# wootch_v_0_0.net
KiCad netlist of a schematic drawn in Altium Designer
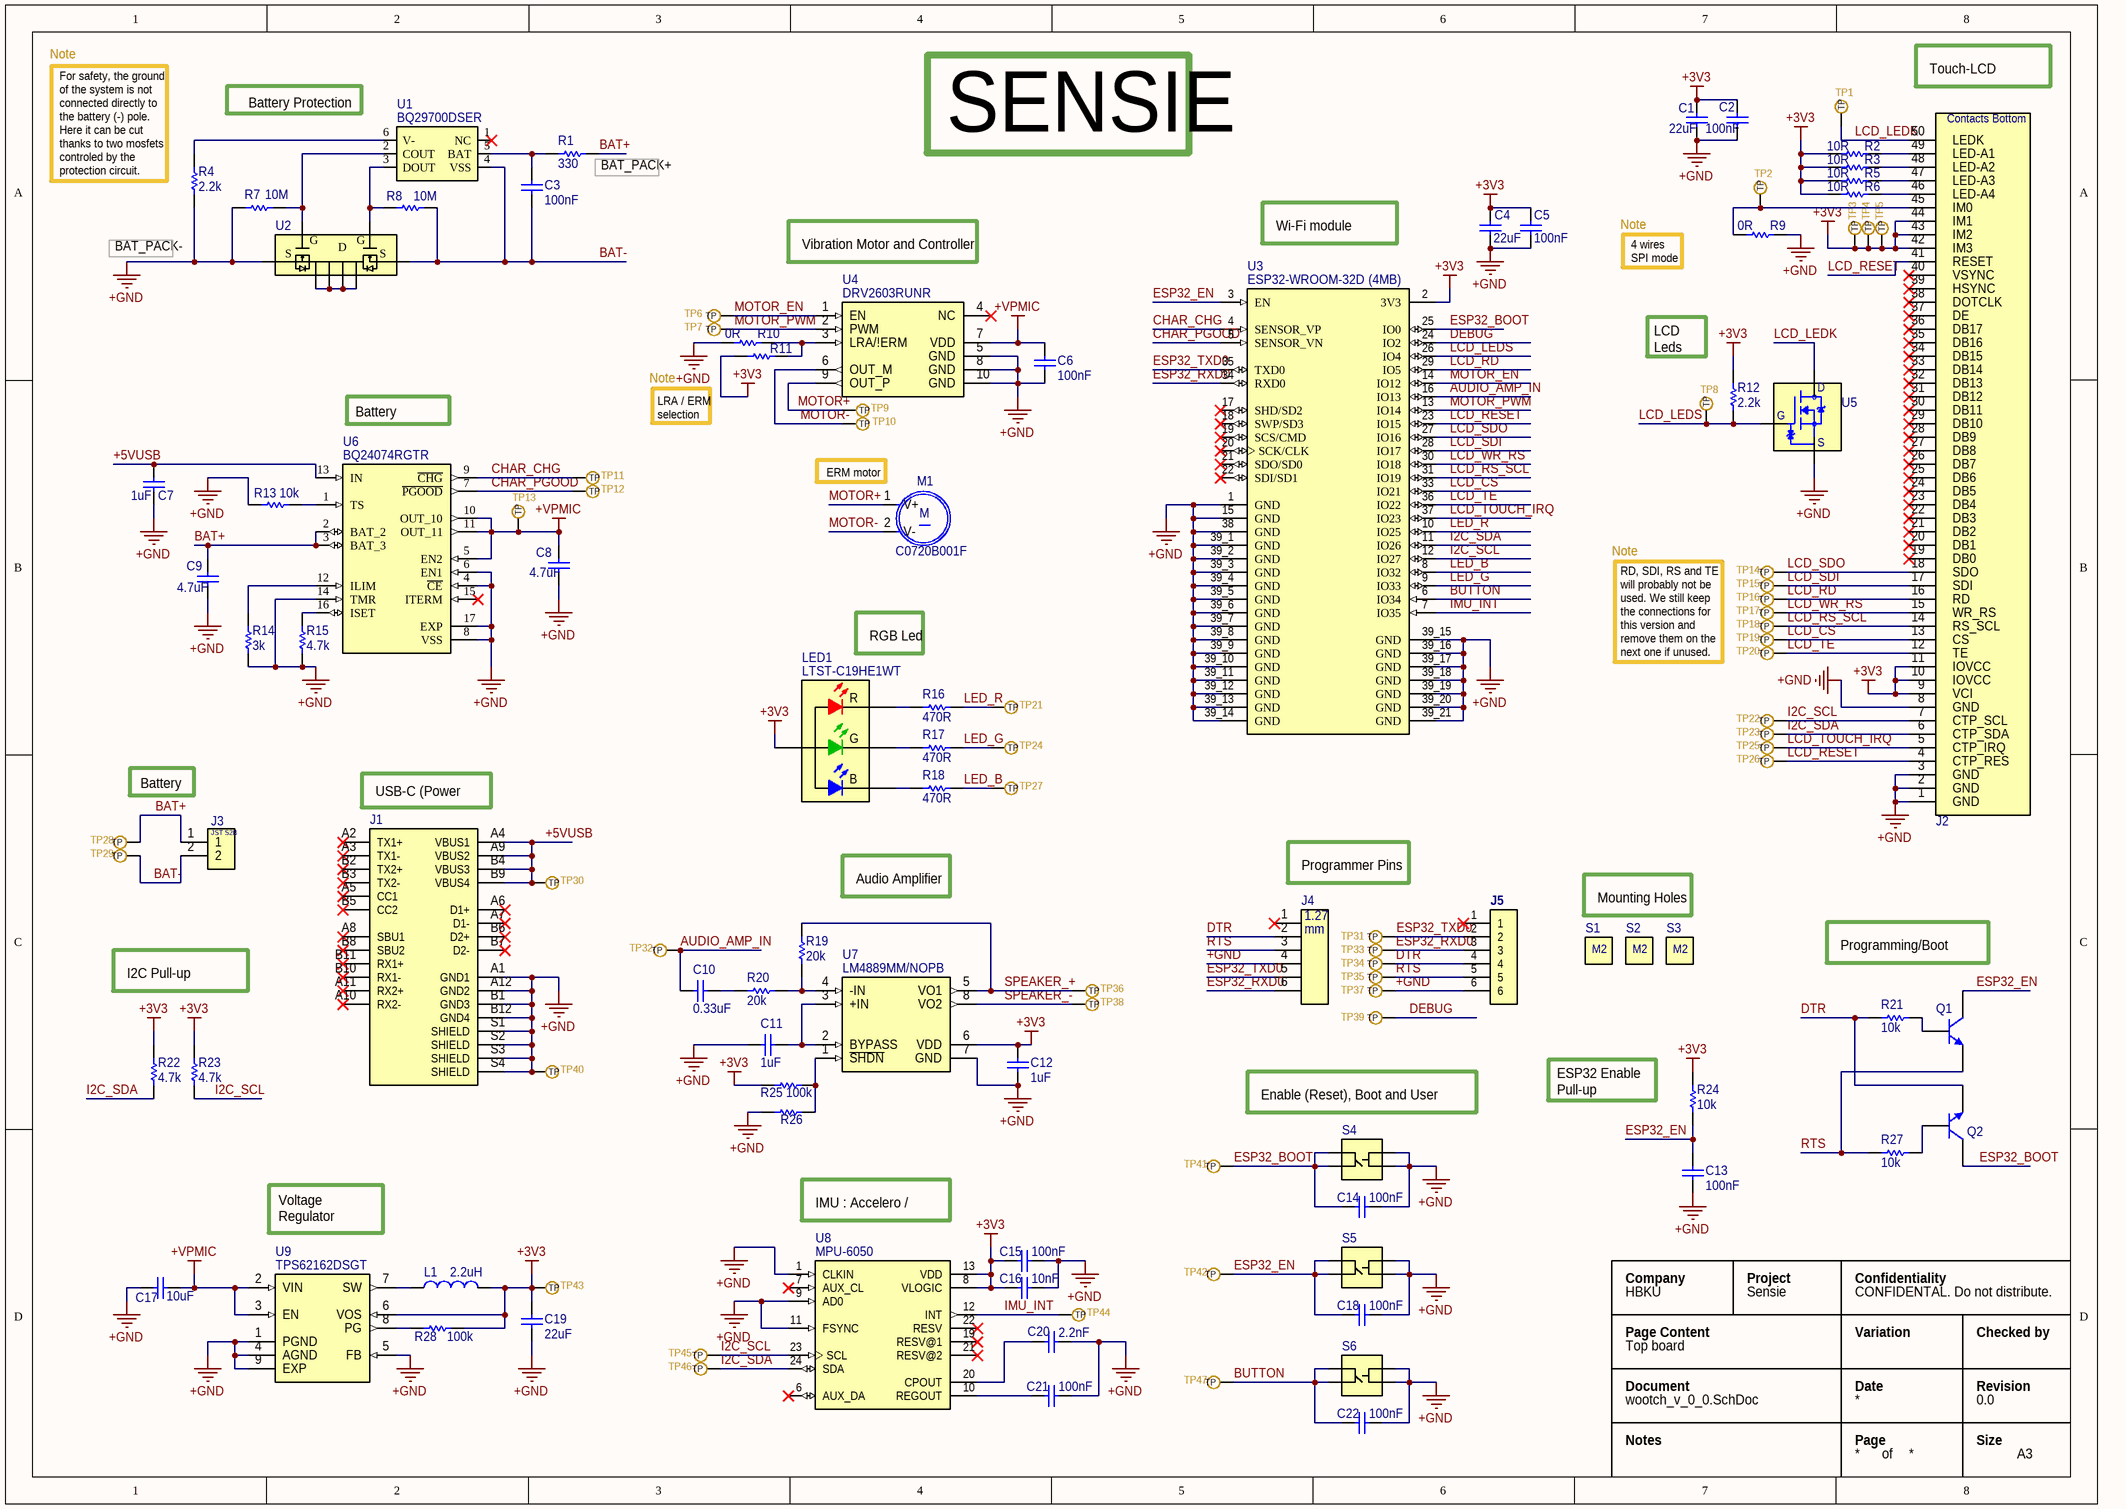
[diagram p0: wootch_v_0_0.SchDoc]

(export (version "E")
  (design (tool "Eeschema 10.0.6"))
  (components
    (comp (ref "C1")
      (value "22uF")
      (footprint "C0603")
      (description "CAP CER 22UF 6.3V X5R 0603")
      (fields
        (field (name "MANUFACTURER PART NUMBER") "GRM188R60J226MEA0D")
        (field (name "MANUFACTURER") "Murata Electronics")
      )
      (libsource (lib "rcl") (part "CAP 22uF 0603"))
    )
    (comp (ref "C2")
      (value "100nF")
      (footprint "C0402")
      (description "CAP CER 0.1UF 16V X7R 0402")
      (fields
        (field (name "MANUFACTURER PART NUMBER") "GRM155R71C104KA88J")
        (field (name "MANUFACTURER") "Murata Electronics")
      )
      (libsource (lib "rcl") (part "CAP 100nF 0402"))
    )
    (comp (ref "C3")
      (value "100nF")
      (footprint "C0402")
      (description "CAP CER 0.1UF 16V X7R 0402")
      (fields
        (field (name "MANUFACTURER PART NUMBER") "GRM155R71C104KA88J")
        (field (name "MANUFACTURER") "Murata Electronics")
      )
      (libsource (lib "rcl") (part "CAP 100nF 0402"))
    )
    (comp (ref "C4")
      (value "22uF")
      (footprint "C0603")
      (description "CAP CER 22UF 6.3V X5R 0603")
      (fields
        (field (name "MANUFACTURER PART NUMBER") "GRM188R60J226MEA0D")
        (field (name "MANUFACTURER") "Murata Electronics")
      )
      (libsource (lib "rcl") (part "CAP 22uF 0603"))
    )
    (comp (ref "C5")
      (value "100nF")
      (footprint "C0402")
      (description "CAP CER 0.1UF 16V X7R 0402")
      (fields
        (field (name "MANUFACTURER PART NUMBER") "GRM155R71C104KA88J")
        (field (name "MANUFACTURER") "Murata Electronics")
      )
      (libsource (lib "rcl") (part "CAP 100nF 0402"))
    )
    (comp (ref "C6")
      (value "100nF")
      (footprint "C0402")
      (description "CAP CER 0.1UF 16V X7R 0402")
      (fields
        (field (name "MANUFACTURER PART NUMBER") "GRM155R71C104KA88J")
        (field (name "MANUFACTURER") "Murata Electronics")
      )
      (libsource (lib "rcl") (part "CAP 100nF 0402"))
    )
    (comp (ref "C7")
      (value "1uF")
      (footprint "C0402")
      (description "CAP CER 1UF 10V X6S 0402")
      (fields
        (field (name "MANUFACTURER PART NUMBER") "GRM155C81A105KA12D")
        (field (name "MANUFACTURER") "Murata Electronics")
      )
      (libsource (lib "rcl") (part "CAP 1uF 0402"))
    )
    (comp (ref "C8")
      (value "4.7uF")
      (footprint "C0402")
      (description "CAP CER 4.7UF 6.3V X5R 0402")
      (fields
        (field (name "MANUFACTURER PART NUMBER") "GRM155R60J475ME47D")
        (field (name "MANUFACTURER") "Murata Electronics")
      )
      (libsource (lib "rcl") (part "CAP 4.7uF 0402"))
    )
    (comp (ref "C9")
      (value "4.7uF")
      (footprint "C0402")
      (description "CAP CER 4.7UF 6.3V X5R 0402")
      (fields
        (field (name "MANUFACTURER PART NUMBER") "GRM155R60J475ME47D")
        (field (name "MANUFACTURER") "Murata Electronics")
      )
      (libsource (lib "rcl") (part "CAP 4.7uF 0402"))
    )
    (comp (ref "C10")
      (value "0.33uF")
      (footprint "C0402")
      (description "CAP CER 0.33UF 10V X6S 0402")
      (fields
        (field (name "MANUFACTURER PART NUMBER") "GRM155R61A334KE15D")
        (field (name "MANUFACTURER") "Murata Electronics")
      )
      (libsource (lib "rcl") (part "CAP 0.33uF 0402"))
    )
    (comp (ref "C11")
      (value "1uF")
      (footprint "C0402")
      (description "CAP CER 1UF 10V X6S 0402")
      (fields
        (field (name "MANUFACTURER PART NUMBER") "GRM155C81A105KA12D")
        (field (name "MANUFACTURER") "Murata Electronics")
      )
      (libsource (lib "rcl") (part "CAP 1uF 0402"))
    )
    (comp (ref "C12")
      (value "1uF")
      (footprint "C0402")
      (description "CAP CER 1UF 10V X6S 0402")
      (fields
        (field (name "MANUFACTURER PART NUMBER") "GRM155C81A105KA12D")
        (field (name "MANUFACTURER") "Murata Electronics")
      )
      (libsource (lib "rcl") (part "CAP 1uF 0402"))
    )
    (comp (ref "C13")
      (value "100nF")
      (footprint "C0402")
      (description "CAP CER 0.1UF 16V X7R 0402")
      (fields
        (field (name "MANUFACTURER PART NUMBER") "GRM155R71C104KA88J")
        (field (name "MANUFACTURER") "Murata Electronics")
      )
      (libsource (lib "rcl") (part "CAP 100nF 0402"))
    )
    (comp (ref "C14")
      (value "100nF")
      (footprint "C0402")
      (description "CAP CER 0.1UF 16V X7R 0402")
      (fields
        (field (name "MANUFACTURER PART NUMBER") "GRM155R71C104KA88J")
        (field (name "MANUFACTURER") "Murata Electronics")
      )
      (libsource (lib "rcl") (part "CAP 100nF 0402"))
    )
    (comp (ref "C15")
      (value "100nF")
      (footprint "C0402")
      (description "CAP CER 0.1UF 16V X7R 0402")
      (fields
        (field (name "MANUFACTURER PART NUMBER") "GRM155R71C104KA88J")
        (field (name "MANUFACTURER") "Murata Electronics")
      )
      (libsource (lib "rcl") (part "CAP 100nF 0402"))
    )
    (comp (ref "C16")
      (value "10nF")
      (footprint "C0402")
      (description "CAP CER 10nF 16V X7R 0402")
      (fields
        (field (name "MANUFACTURER PART NUMBER") "GCM155R71H103KA55D")
        (field (name "MANUFACTURER") "Murata Electronics")
      )
      (libsource (lib "rcl") (part "CAP 10nF 0402"))
    )
    (comp (ref "C17")
      (value "10uF")
      (footprint "C0402")
      (description "CAP CER 10UF 4V X5R 0402")
      (fields
        (field (name "MANUFACTURER PART NUMBER") "GRM155R60G106ME44D")
        (field (name "MANUFACTURER") "Murata Electronics")
      )
      (libsource (lib "rcl") (part "CAP 10uF 0402"))
    )
    (comp (ref "C18")
      (value "100nF")
      (footprint "C0402")
      (description "CAP CER 0.1UF 16V X7R 0402")
      (fields
        (field (name "MANUFACTURER PART NUMBER") "GRM155R71C104KA88J")
        (field (name "MANUFACTURER") "Murata Electronics")
      )
      (libsource (lib "rcl") (part "CAP 100nF 0402"))
    )
    (comp (ref "C19")
      (value "22uF")
      (footprint "C0603")
      (description "CAP CER 22UF 6.3V X5R 0603")
      (fields
        (field (name "MANUFACTURER PART NUMBER") "GRM188R60J226MEA0D")
        (field (name "MANUFACTURER") "Murata Electronics")
      )
      (libsource (lib "rcl") (part "CAP 22uF 0603"))
    )
    (comp (ref "C20")
      (value "2.2nF")
      (footprint "C0402")
      (description "CAP CER 2.2nF 16V X7R 0402")
      (fields
        (field (name "MANUFACTURER PART NUMBER") "GCM155R72A222KA37D")
        (field (name "MANUFACTURER") "Murata Electronics")
      )
      (libsource (lib "rcl") (part "CAP 2.2nF 0402"))
    )
    (comp (ref "C21")
      (value "100nF")
      (footprint "C0402")
      (description "CAP CER 0.1UF 16V X7R 0402")
      (fields
        (field (name "MANUFACTURER PART NUMBER") "GRM155R71C104KA88J")
        (field (name "MANUFACTURER") "Murata Electronics")
      )
      (libsource (lib "rcl") (part "CAP 100nF 0402"))
    )
    (comp (ref "C22")
      (value "100nF")
      (footprint "C0402")
      (description "CAP CER 0.1UF 16V X7R 0402")
      (fields
        (field (name "MANUFACTURER PART NUMBER") "GRM155R71C104KA88J")
        (field (name "MANUFACTURER") "Murata Electronics")
      )
      (libsource (lib "rcl") (part "CAP 100nF 0402"))
    )
    (comp (ref "J1")
      (value "1054500101")
      (footprint "USB-C-1054500101")
      (description "USB-C CONN RCP USB3.1 TYPEC 24P SMD RA")
      (fields (field (name "MANUFACTURER") "Molex"))
      (libsource (lib "connectors") (part "1054500101"))
    )
    (comp (ref "J2")
      (value "FPC-50-screen-connector-bottom-62684-501100ALF")
      (footprint "FPC-50-62684-501100ALF")
      (description "FPC CONN BOTTOM 50POS 0.50MM R/A")
      (fields
        (field (name "MANUFACTURER") "Amphenol ICC (FCI)")
        (field (name "MANUFACTURER PART NUMBER") "62684-501100ALF")
      )
      (libsource (lib "connectors") (part "FPC-50-screen-connector-bottom-62684-501100ALF"))
    )
    (comp (ref "J3")
      (value "S2B-PH-K-S(LF)(SN)")
      (footprint "S2B-PH-K-S(LF)(SN)")
      (description "JST 2mm CONN HEADER R/A 2POS")
      (fields (field (name "MANUFACTURER") "JST Sales America Inc."))
      (libsource (lib "connectors") (part "S2B-PH-K-S(LF)(SN)"))
    )
    (comp (ref "J4")
      (value "FTS-103-01-F-DV-TR")
      (footprint "CON_6_2_1.27_FTS_103_01")
      (description "CONN HEADER SMD 6POS 1.27MM")
      (fields (field (name "MANUFACTURER") "Samtec Inc."))
      (libsource (lib "connectors") (part "FTS-103-01-F-DV-TR"))
    )
    (comp (ref "J5")
      (value "Plug of Nails 6 pins")
      (footprint "PLUG-OF-NAILS-6-PIN")
      (description "CBL PLUG-OF-NAILS 6-PIN with NO ATTACHMENT holes (contrary to the digikey link)")
      (fields
        (field (name "MANUFACTURER") "Tag-Connect LLC")
        (field (name "MANUFACTURER PART NUMBER") "TC2030-CTX")
      )
      (libsource (lib "connectors") (part "Plug of Nails 6 pins"))
    )
    (comp (ref "L1")
      (value "2.2uH")
      (footprint "L0603")
      (description "2.2UH20% 1.05A(MAX) / 1.15A(TYP.")
      (fields
        (field (name "MANUFACTURER") "Murata Electronics")
        (field (name "MANUFACTURER PART NUMBER") "LQM18PN2R2MGHD")
      )
      (libsource (lib "rcl") (part "IND 2.2uH 0603"))
    )
    (comp (ref "LED1")
      (value "rgb_LTST-C19HE1WT")
      (footprint "LTST-C19HE1WT-4_V")
      (fields
        (field (name "MANUFACTURER") "Lite-On Inc.")
        (field (name "MANUFACTURER PART NUMBER") "LTST-C19HE1WT")
      )
      (libsource (lib "chips") (part "rgb_LTST-C19HE1WT"))
    )
    (comp (ref "M1")
      (value "C0720B001F")
      (footprint "C0720B001F")
      (description "DC Motor Vibration, ERM 10000 RPM   3VDC")
      (fields
        (field (name "MANUFACTURER") "Jinlong Machinery & Electronics, Inc.")
        (field (name "MANUFACTURER PART NUMBER") "C0720B001F")
      )
      (libsource (lib "miscellaneaous") (part "C0720B001F"))
    )
    (comp (ref "Q1")
      (value "MMBT2222ALT1G")
      (footprint "ONSC-SOT-23-3-318-08_V")
      (fields (field (name "MANUFACTURER") "ON Semiconductor"))
      (libsource (lib "chips") (part "MMBT2222ALT1G"))
    )
    (comp (ref "Q2")
      (value "MMBT2222ALT1G")
      (footprint "ONSC-SOT-23-3-318-08_V")
      (fields (field (name "MANUFACTURER") "ON Semiconductor"))
      (libsource (lib "chips") (part "MMBT2222ALT1G"))
    )
    (comp (ref "R1")
      (value "330")
      (footprint "R0402")
      (description "RES SMD 330 OHM 1% 1/16W 0402")
      (fields
        (field (name "MANUFACTURER") "Yageo")
        (field (name "MANUFACTURER PART NUMBER") "RC0402FR-07330RL")
      )
      (libsource (lib "rcl") (part "RES 330R 0402"))
    )
    (comp (ref "R2")
      (value "10R")
      (footprint "R0402")
      (description "RES SMD 10 OHM 1% 1/16W 0402")
      (fields
        (field (name "MANUFACTURER") "Yageo")
        (field (name "MANUFACTURER PART NUMBER") "RC0402FR-0710RL")
      )
      (libsource (lib "rcl") (part "RES 10R 0402"))
    )
    (comp (ref "R3")
      (value "10R")
      (footprint "R0402")
      (description "RES SMD 10 OHM 1% 1/16W 0402")
      (fields
        (field (name "MANUFACTURER") "Yageo")
        (field (name "MANUFACTURER PART NUMBER") "RC0402FR-0710RL")
      )
      (libsource (lib "rcl") (part "RES 10R 0402"))
    )
    (comp (ref "R4")
      (value "2.2k")
      (footprint "R0402")
      (description "RES SMD 2.2K OHM 1% 1/16W 0402")
      (fields
        (field (name "MANUFACTURER") "Yageo")
        (field (name "MANUFACTURER PART NUMBER") "RC0402FR-072K2L")
      )
      (libsource (lib "rcl") (part "RES 2.2k 0402"))
    )
    (comp (ref "R5")
      (value "10R")
      (footprint "R0402")
      (description "RES SMD 10 OHM 1% 1/16W 0402")
      (fields
        (field (name "MANUFACTURER") "Yageo")
        (field (name "MANUFACTURER PART NUMBER") "RC0402FR-0710RL")
      )
      (libsource (lib "rcl") (part "RES 10R 0402"))
    )
    (comp (ref "R6")
      (value "10R")
      (footprint "R0402")
      (description "RES SMD 10 OHM 1% 1/16W 0402")
      (fields
        (field (name "MANUFACTURER") "Yageo")
        (field (name "MANUFACTURER PART NUMBER") "RC0402FR-0710RL")
      )
      (libsource (lib "rcl") (part "RES 10R 0402"))
    )
    (comp (ref "R7")
      (value "10M")
      (footprint "R0402")
      (description "RES SMD 10 MOHM 1% 1/16W 0402")
      (fields
        (field (name "MANUFACTURER") "Yageo")
        (field (name "MANUFACTURER PART NUMBER") "RC0402FR-0710ML")
      )
      (libsource (lib "rcl") (part "RES 10M 0402"))
    )
    (comp (ref "R8")
      (value "10M")
      (footprint "R0402")
      (description "RES SMD 10 MOHM 1% 1/16W 0402")
      (fields
        (field (name "MANUFACTURER") "Yageo")
        (field (name "MANUFACTURER PART NUMBER") "RC0402FR-0710ML")
      )
      (libsource (lib "rcl") (part "RES 10M 0402"))
    )
    (comp (ref "R9")
      (value "0R")
      (footprint "R0402")
      (description "RES SMD 0 OHM JUMPER 1/16W 0402")
      (fields
        (field (name "MANUFACTURER") "Yageo")
        (field (name "MANUFACTURER PART NUMBER") "RC0402JR-070RL")
      )
      (libsource (lib "rcl") (part "RES 0R 0402"))
    )
    (comp (ref "R10")
      (value "0R")
      (footprint "R0402")
      (description "RES SMD 0 OHM JUMPER 1/16W 0402")
      (fields
        (field (name "MANUFACTURER") "Yageo")
        (field (name "MANUFACTURER PART NUMBER") "RC0402JR-070RL")
      )
      (libsource (lib "rcl") (part "RES 0R 0402"))
    )
    (comp (ref "R11")
      (value "Thick Film")
      (footprint "R0402_DNI")
      (description "DNI (Do Not Install)")
      (libsource (lib "rcl") (part "RES DNI 0402"))
    )
    (comp (ref "R12")
      (value "2.2k")
      (footprint "R0402")
      (description "RES SMD 2.2K OHM 1% 1/16W 0402")
      (fields
        (field (name "MANUFACTURER") "Yageo")
        (field (name "MANUFACTURER PART NUMBER") "RC0402FR-072K2L")
      )
      (libsource (lib "rcl") (part "RES 2.2k 0402"))
    )
    (comp (ref "R13")
      (value "10k")
      (footprint "R0402")
      (description "RES SMD 10K OHM 1% 1/16W 0402")
      (fields
        (field (name "MANUFACTURER") "Yageo")
        (field (name "MANUFACTURER PART NUMBER") "RC0402FR-0710KL")
      )
      (libsource (lib "rcl") (part "RES 10k 0402"))
    )
    (comp (ref "R14")
      (value "3k")
      (footprint "R0402")
      (description "RES SMD 10K OHM 1% 1/16W 0402")
      (fields
        (field (name "MANUFACTURER") "Yageo")
        (field (name "MANUFACTURER PART NUMBER") "RC0402FR-073KL")
      )
      (libsource (lib "rcl") (part "RES 3k 0402"))
    )
    (comp (ref "R15")
      (value "4.7k")
      (footprint "R0402")
      (description "RES SMD 4.7K OHM 1% 1/16W 0402")
      (fields
        (field (name "MANUFACTURER") "Yageo")
        (field (name "MANUFACTURER PART NUMBER") "RT0402FRE074K7L")
      )
      (libsource (lib "rcl") (part "RES 4.7k 0402"))
    )
    (comp (ref "R16")
      (value "470R")
      (footprint "R0402")
      (description "RES SMD 470 OHM 1% 1/16W 0402")
      (fields
        (field (name "MANUFACTURER") "Yageo")
        (field (name "MANUFACTURER PART NUMBER") "RC0402FR-07470RL")
      )
      (libsource (lib "rcl") (part "RES 470R 0402"))
    )
    (comp (ref "R17")
      (value "470R")
      (footprint "R0402")
      (description "RES SMD 470 OHM 1% 1/16W 0402")
      (fields
        (field (name "MANUFACTURER") "Yageo")
        (field (name "MANUFACTURER PART NUMBER") "RC0402FR-07470RL")
      )
      (libsource (lib "rcl") (part "RES 470R 0402"))
    )
    (comp (ref "R18")
      (value "470R")
      (footprint "R0402")
      (description "RES SMD 470 OHM 1% 1/16W 0402")
      (fields
        (field (name "MANUFACTURER") "Yageo")
        (field (name "MANUFACTURER PART NUMBER") "RC0402FR-07470RL")
      )
      (libsource (lib "rcl") (part "RES 470R 0402"))
    )
    (comp (ref "R19")
      (value "20k")
      (footprint "R0402")
      (description "RES SMD 20K OHM 1% 1/16W 0402")
      (fields
        (field (name "MANUFACTURER") "Yageo")
        (field (name "MANUFACTURER PART NUMBER") "RC0402FR-0720KL")
      )
      (libsource (lib "rcl") (part "RES 20k 0402"))
    )
    (comp (ref "R20")
      (value "20k")
      (footprint "R0402")
      (description "RES SMD 20K OHM 1% 1/16W 0402")
      (fields
        (field (name "MANUFACTURER") "Yageo")
        (field (name "MANUFACTURER PART NUMBER") "RC0402FR-0720KL")
      )
      (libsource (lib "rcl") (part "RES 20k 0402"))
    )
    (comp (ref "R21")
      (value "10k")
      (footprint "R0402")
      (description "RES SMD 10K OHM 1% 1/16W 0402")
      (fields
        (field (name "MANUFACTURER") "Yageo")
        (field (name "MANUFACTURER PART NUMBER") "RC0402FR-0710KL")
      )
      (libsource (lib "rcl") (part "RES 10k 0402"))
    )
    (comp (ref "R22")
      (value "4.7k")
      (footprint "R0402")
      (description "RES SMD 4.7K OHM 1% 1/16W 0402")
      (fields
        (field (name "MANUFACTURER") "Yageo")
        (field (name "MANUFACTURER PART NUMBER") "RT0402FRE074K7L")
      )
      (libsource (lib "rcl") (part "RES 4.7k 0402"))
    )
    (comp (ref "R23")
      (value "4.7k")
      (footprint "R0402")
      (description "RES SMD 4.7K OHM 1% 1/16W 0402")
      (fields
        (field (name "MANUFACTURER") "Yageo")
        (field (name "MANUFACTURER PART NUMBER") "RT0402FRE074K7L")
      )
      (libsource (lib "rcl") (part "RES 4.7k 0402"))
    )
    (comp (ref "R24")
      (value "10k")
      (footprint "R0402")
      (description "RES SMD 10K OHM 1% 1/16W 0402")
      (fields
        (field (name "MANUFACTURER") "Yageo")
        (field (name "MANUFACTURER PART NUMBER") "RC0402FR-0710KL")
      )
      (libsource (lib "rcl") (part "RES 10k 0402"))
    )
    (comp (ref "R25")
      (value "100k")
      (footprint "R0402")
      (description "RES SMD 100K OHM 1% 1/16W 0402")
      (fields
        (field (name "MANUFACTURER") "Yageo")
        (field (name "MANUFACTURER PART NUMBER") "RC0402FR-07100KL")
      )
      (libsource (lib "rcl") (part "RES 100k 0402"))
    )
    (comp (ref "R26")
      (value "Thick Film")
      (footprint "R0402_DNI")
      (description "DNI (Do Not Install)")
      (libsource (lib "rcl") (part "RES DNI 0402"))
    )
    (comp (ref "R27")
      (value "10k")
      (footprint "R0402")
      (description "RES SMD 10K OHM 1% 1/16W 0402")
      (fields
        (field (name "MANUFACTURER") "Yageo")
        (field (name "MANUFACTURER PART NUMBER") "RC0402FR-0710KL")
      )
      (libsource (lib "rcl") (part "RES 10k 0402"))
    )
    (comp (ref "R28")
      (value "100k")
      (footprint "R0402")
      (description "RES SMD 100K OHM 1% 1/16W 0402")
      (fields
        (field (name "MANUFACTURER") "Yageo")
        (field (name "MANUFACTURER PART NUMBER") "RC0402FR-07100KL")
      )
      (libsource (lib "rcl") (part "RES 100k 0402"))
    )
    (comp (ref "S1")
      (value "hole_M2")
      (footprint "M2_no_screw")
      (description "Mounting hole  M2 size, no solder stop, so no screw")
      (libsource (lib "connectors") (part "hole_M2"))
    )
    (comp (ref "S2")
      (value "hole_M2")
      (footprint "M2_no_screw")
      (description "Mounting hole  M2 size, no solder stop, so no screw")
      (libsource (lib "connectors") (part "hole_M2"))
    )
    (comp (ref "S3")
      (value "hole_M2")
      (footprint "M2_no_screw")
      (description "Mounting hole  M2 size, no solder stop, so no screw")
      (libsource (lib "connectors") (part "hole_M2"))
    )
    (comp (ref "S4")
      (value "TL1014BF160QG")
      (footprint "BUTTON_TL1014BF160QG")
      (description "SWITCH TACTILE SPST-NO 0.05A 12V")
      (fields (field (name "MANUFACTURER") "E-Switch"))
      (libsource (lib "miscellaneaous") (part "TL1014BF160QG"))
    )
    (comp (ref "S5")
      (value "TL1014BF160QG")
      (footprint "BUTTON_TL1014BF160QG")
      (description "SWITCH TACTILE SPST-NO 0.05A 12V")
      (fields (field (name "MANUFACTURER") "E-Switch"))
      (libsource (lib "miscellaneaous") (part "TL1014BF160QG"))
    )
    (comp (ref "S6")
      (value "TL1014BF160QG")
      (footprint "BUTTON_TL1014BF160QG")
      (description "SWITCH TACTILE SPST-NO 0.05A 12V")
      (fields (field (name "MANUFACTURER") "E-Switch"))
      (libsource (lib "miscellaneaous") (part "TL1014BF160QG"))
    )
    (comp (ref "TP1")
      (value "TP_1mm")
      (footprint "TP_1mm")
      (description "Test point 1mm diameter")
      (libsource (lib "miscellaneaous") (part "TP_1mm"))
    )
    (comp (ref "TP2")
      (value "TP_1mm")
      (footprint "TP_1mm")
      (description "Test point 1mm diameter")
      (libsource (lib "miscellaneaous") (part "TP_1mm"))
    )
    (comp (ref "TP3")
      (value "TP_1mm")
      (footprint "TP_1mm")
      (description "Test point 1mm diameter")
      (libsource (lib "miscellaneaous") (part "TP_1mm"))
    )
    (comp (ref "TP4")
      (value "TP_1mm")
      (footprint "TP_1mm")
      (description "Test point 1mm diameter")
      (libsource (lib "miscellaneaous") (part "TP_1mm"))
    )
    (comp (ref "TP5")
      (value "TP_1mm")
      (footprint "TP_1mm")
      (description "Test point 1mm diameter")
      (libsource (lib "miscellaneaous") (part "TP_1mm"))
    )
    (comp (ref "TP6")
      (value "TP_1mm")
      (footprint "TP_1mm")
      (description "Test point 1mm diameter")
      (libsource (lib "miscellaneaous") (part "TP_1mm"))
    )
    (comp (ref "TP7")
      (value "TP_1mm")
      (footprint "TP_1mm")
      (description "Test point 1mm diameter")
      (libsource (lib "miscellaneaous") (part "TP_1mm"))
    )
    (comp (ref "TP8")
      (value "TP_1mm")
      (footprint "TP_1mm")
      (description "Test point 1mm diameter")
      (libsource (lib "miscellaneaous") (part "TP_1mm"))
    )
    (comp (ref "TP9")
      (value "TP_2mm")
      (footprint "TP_2mm")
      (description "Test point 2mm diameter")
      (libsource (lib "miscellaneaous") (part "TP_2mm"))
    )
    (comp (ref "TP10")
      (value "TP_2mm")
      (footprint "TP_2mm")
      (description "Test point 2mm diameter")
      (libsource (lib "miscellaneaous") (part "TP_2mm"))
    )
    (comp (ref "TP11")
      (value "TP_1mm")
      (footprint "TP_1mm")
      (description "Test point 1mm diameter")
      (libsource (lib "miscellaneaous") (part "TP_1mm"))
    )
    (comp (ref "TP12")
      (value "TP_1mm")
      (footprint "TP_1mm")
      (description "Test point 1mm diameter")
      (libsource (lib "miscellaneaous") (part "TP_1mm"))
    )
    (comp (ref "TP13")
      (value "TP_1mm")
      (footprint "TP_1mm")
      (description "Test point 1mm diameter")
      (libsource (lib "miscellaneaous") (part "TP_1mm"))
    )
    (comp (ref "TP14")
      (value "TP_1mm")
      (footprint "TP_1mm")
      (description "Test point 1mm diameter")
      (libsource (lib "miscellaneaous") (part "TP_1mm"))
    )
    (comp (ref "TP15")
      (value "TP_1mm")
      (footprint "TP_1mm")
      (description "Test point 1mm diameter")
      (libsource (lib "miscellaneaous") (part "TP_1mm"))
    )
    (comp (ref "TP16")
      (value "TP_1mm")
      (footprint "TP_1mm")
      (description "Test point 1mm diameter")
      (libsource (lib "miscellaneaous") (part "TP_1mm"))
    )
    (comp (ref "TP17")
      (value "TP_1mm")
      (footprint "TP_1mm")
      (description "Test point 1mm diameter")
      (libsource (lib "miscellaneaous") (part "TP_1mm"))
    )
    (comp (ref "TP18")
      (value "TP_1mm")
      (footprint "TP_1mm")
      (description "Test point 1mm diameter")
      (libsource (lib "miscellaneaous") (part "TP_1mm"))
    )
    (comp (ref "TP19")
      (value "TP_1mm")
      (footprint "TP_1mm")
      (description "Test point 1mm diameter")
      (libsource (lib "miscellaneaous") (part "TP_1mm"))
    )
    (comp (ref "TP20")
      (value "TP_1mm")
      (footprint "TP_1mm")
      (description "Test point 1mm diameter")
      (libsource (lib "miscellaneaous") (part "TP_1mm"))
    )
    (comp (ref "TP21")
      (value "TP_1mm")
      (footprint "TP_1mm")
      (description "Test point 1mm diameter")
      (libsource (lib "miscellaneaous") (part "TP_1mm"))
    )
    (comp (ref "TP22")
      (value "TP_1mm")
      (footprint "TP_1mm")
      (description "Test point 1mm diameter")
      (libsource (lib "miscellaneaous") (part "TP_1mm"))
    )
    (comp (ref "TP23")
      (value "TP_1mm")
      (footprint "TP_1mm")
      (description "Test point 1mm diameter")
      (libsource (lib "miscellaneaous") (part "TP_1mm"))
    )
    (comp (ref "TP24")
      (value "TP_1mm")
      (footprint "TP_1mm")
      (description "Test point 1mm diameter")
      (libsource (lib "miscellaneaous") (part "TP_1mm"))
    )
    (comp (ref "TP25")
      (value "TP_1mm")
      (footprint "TP_1mm")
      (description "Test point 1mm diameter")
      (libsource (lib "miscellaneaous") (part "TP_1mm"))
    )
    (comp (ref "TP26")
      (value "TP_1mm")
      (footprint "TP_1mm")
      (description "Test point 1mm diameter")
      (libsource (lib "miscellaneaous") (part "TP_1mm"))
    )
    (comp (ref "TP27")
      (value "TP_1mm")
      (footprint "TP_1mm")
      (description "Test point 1mm diameter")
      (libsource (lib "miscellaneaous") (part "TP_1mm"))
    )
    (comp (ref "TP28")
      (value "TP_3mm")
      (footprint "TP_3mm")
      (description "Test point 2mm diameter")
      (libsource (lib "miscellaneaous") (part "TP_3mm"))
    )
    (comp (ref "TP29")
      (value "TP_3mm")
      (footprint "TP_3mm")
      (description "Test point 2mm diameter")
      (libsource (lib "miscellaneaous") (part "TP_3mm"))
    )
    (comp (ref "TP30")
      (value "TP_1mm")
      (footprint "TP_1mm")
      (description "Test point 1mm diameter")
      (libsource (lib "miscellaneaous") (part "TP_1mm"))
    )
    (comp (ref "TP31")
      (value "TP_2mm")
      (footprint "TP_2mm")
      (description "Test point 2mm diameter")
      (libsource (lib "miscellaneaous") (part "TP_2mm"))
    )
    (comp (ref "TP32")
      (value "TP_1mm")
      (footprint "TP_1mm")
      (description "Test point 1mm diameter")
      (libsource (lib "miscellaneaous") (part "TP_1mm"))
    )
    (comp (ref "TP33")
      (value "TP_2mm")
      (footprint "TP_2mm")
      (description "Test point 2mm diameter")
      (libsource (lib "miscellaneaous") (part "TP_2mm"))
    )
    (comp (ref "TP34")
      (value "TP_2mm")
      (footprint "TP_2mm")
      (description "Test point 2mm diameter")
      (libsource (lib "miscellaneaous") (part "TP_2mm"))
    )
    (comp (ref "TP35")
      (value "TP_2mm")
      (footprint "TP_2mm")
      (description "Test point 2mm diameter")
      (libsource (lib "miscellaneaous") (part "TP_2mm"))
    )
    (comp (ref "TP36")
      (value "TP_2mm")
      (footprint "TP_2mm")
      (description "Test point 2mm diameter")
      (libsource (lib "miscellaneaous") (part "TP_2mm"))
    )
    (comp (ref "TP37")
      (value "TP_2mm")
      (footprint "TP_2mm")
      (description "Test point 2mm diameter")
      (libsource (lib "miscellaneaous") (part "TP_2mm"))
    )
    (comp (ref "TP38")
      (value "TP_2mm")
      (footprint "TP_2mm")
      (description "Test point 2mm diameter")
      (libsource (lib "miscellaneaous") (part "TP_2mm"))
    )
    (comp (ref "TP39")
      (value "TP_2mm")
      (footprint "TP_2mm")
      (description "Test point 2mm diameter")
      (libsource (lib "miscellaneaous") (part "TP_2mm"))
    )
    (comp (ref "TP40")
      (value "TP_1mm")
      (footprint "TP_1mm")
      (description "Test point 1mm diameter")
      (libsource (lib "miscellaneaous") (part "TP_1mm"))
    )
    (comp (ref "TP41")
      (value "TP_1mm")
      (footprint "TP_1mm")
      (description "Test point 1mm diameter")
      (libsource (lib "miscellaneaous") (part "TP_1mm"))
    )
    (comp (ref "TP42")
      (value "TP_1mm")
      (footprint "TP_1mm")
      (description "Test point 1mm diameter")
      (libsource (lib "miscellaneaous") (part "TP_1mm"))
    )
    (comp (ref "TP43")
      (value "TP_1mm")
      (footprint "TP_1mm")
      (description "Test point 1mm diameter")
      (libsource (lib "miscellaneaous") (part "TP_1mm"))
    )
    (comp (ref "TP44")
      (value "TP_1mm")
      (footprint "TP_1mm")
      (description "Test point 1mm diameter")
      (libsource (lib "miscellaneaous") (part "TP_1mm"))
    )
    (comp (ref "TP45")
      (value "TP_1mm")
      (footprint "TP_1mm")
      (description "Test point 1mm diameter")
      (libsource (lib "miscellaneaous") (part "TP_1mm"))
    )
    (comp (ref "TP46")
      (value "TP_1mm")
      (footprint "TP_1mm")
      (description "Test point 1mm diameter")
      (libsource (lib "miscellaneaous") (part "TP_1mm"))
    )
    (comp (ref "TP47")
      (value "TP_1mm")
      (footprint "TP_1mm")
      (description "Test point 1mm diameter")
      (libsource (lib "miscellaneaous") (part "TP_1mm"))
    )
    (comp (ref "U1")
      (value "BQ29700DSER")
      (footprint "BATT_PROTEC_BQ29700DSER")
      (description "BATT LITHIUM BATT PROTECT 6-SON")
      (fields (field (name "MANUFACTURER") "Texas Instruments"))
      (libsource (lib "chips") (part "BQ29700DSER"))
    )
    (comp (ref "U2")
      (value "ECH8693R-TL-W")
      (footprint "MOSFET_2CHAN_ECH8693R-TL-W")
      (description "MOSFET 2N-CH 24V 14A SOT-28")
      (fields (field (name "MANUFACTURER") "ON Semiconductor"))
      (libsource (lib "chips") (part "ECH8693R-TL-W"))
    )
    (comp (ref "U3")
      (value "ESP32-WROOM-32D")
      (footprint "ESP32-WROOM-32D (4MB)")
      (description "ESP32-WROOM-32D Wifi/Bluetooth Module")
      (fields
        (field (name "MANUFACTURER") "Espressif Systems")
        (field (name "MANUFACTURER PART NUMBER") "ESP32-WROOM-32D (4MB)")
      )
      (libsource (lib "chips") (part "ESP32-WROOM-32D"))
    )
    (comp (ref "U4")
      (value "DRV2603RUNR")
      (footprint "MOT_DRV_DRV2603RUNR")
      (description "MOTOR DRIVER 2.5V-5.2V 10QFN")
      (fields (field (name "MANUFACTURER") "Texas Instruments"))
      (libsource (lib "chips") (part "DRV2603RUNR"))
    )
    (comp (ref "U5")
      (value "DMG1012UW-7")
      (footprint "MOSFET-DMG1012UW-SOT323")
      (description "MOSFET Logi level N-CH 20V 1A SOT323")
      (fields (field (name "MANUFACTURER") "Diodes Incorporated"))
      (libsource (lib "chips") (part "DMG1012UW-7"))
    )
    (comp (ref "U6")
      (value "BQ24074RGTR")
      (footprint "BATT_CHARG_BQ24074RGTR")
      (description "BATT LI-ION CHARGE MGMT 16-QFN")
      (fields
        (field (name "MANUFACTURER") "Texas Instruments")
        (field (name "MANUFACTURER PART NUMBER") "BQ24074RGTR")
      )
      (libsource (lib "chips") (part "BQ24074RGTR"))
    )
    (comp (ref "U7")
      (value "LM4889")
      (footprint "Amp_LM4889MM")
      (description "IC AMP CLASS AB MONO 1W 8VSSOP")
      (fields
        (field (name "MANUFACTURER") "Texas Instruments")
        (field (name "MANUFACTURER PART NUMBER") "LM4889MM/NOPB")
      )
      (libsource (lib "chips") (part "LM4889"))
    )
    (comp (ref "U8")
      (value "MPU-6050")
      (footprint "MPU6050-ACCELERO-GYRO")
      (description "IMU ACCEL/GYRO 3-AXIS I2C 24QFN")
      (fields
        (field (name "MANUFACTURER") "TDK InvenSense")
        (field (name "MANUFACTURER PART NUMBER") "MPU-6050")
      )
      (libsource (lib "chips") (part "MPU-6050"))
    )
    (comp (ref "U9")
      (value "TPS62162DSGT")
      (footprint "REG_BUCK_TPS62162DSGT")
      (description "IC REG BUCK 3.3V 1A 8WSON")
      (fields
        (field (name "MANUFACTURER") "Texas Instruments")
        (field (name "MANUFACTURER PART NUMBER") "TPS62162DSGT")
      )
      (libsource (lib "chips") (part "TPS62162DSGT"))
    )
  )
  (nets
    (net (code "1") (name "+3V3") (class "Default")
      (node (ref "C1") (pin "2") (pinfunction "2_2") (pintype "passive"))
      (node (ref "C12") (pin "2") (pinfunction "2_2") (pintype "passive"))
      (node (ref "C15") (pin "1") (pinfunction "1_1") (pintype "passive"))
      (node (ref "C16") (pin "1") (pinfunction "1_1") (pintype "passive"))
      (node (ref "C19") (pin "2") (pinfunction "2_2") (pintype "passive"))
      (node (ref "C2") (pin "2") (pinfunction "2_2") (pintype "passive"))
      (node (ref "C4") (pin "2") (pinfunction "2_2") (pintype "passive"))
      (node (ref "C5") (pin "2") (pinfunction "2_2") (pintype "passive"))
      (node (ref "J2") (pin "10") (pinfunction "IOVCC_10") (pintype "passive"))
      (node (ref "J2") (pin "11") (pinfunction "IOVCC_11") (pintype "passive"))
      (node (ref "J2") (pin "42") (pinfunction "IM3_42") (pintype "passive"))
      (node (ref "J2") (pin "43") (pinfunction "IM2_43") (pintype "passive"))
      (node (ref "J2") (pin "44") (pinfunction "IM1_44") (pintype "passive"))
      (node (ref "J2") (pin "9") (pinfunction "VCI_9") (pintype "passive"))
      (node (ref "L1") (pin "2") (pinfunction "2_2") (pintype "passive"))
      (node (ref "LED1") (pin "4") (pinfunction "A_4") (pintype "passive"))
      (node (ref "R11") (pin "1") (pinfunction "1_1") (pintype "passive"))
      (node (ref "R12") (pin "2") (pinfunction "2_2") (pintype "passive"))
      (node (ref "R2") (pin "1") (pinfunction "1_1") (pintype "passive"))
      (node (ref "R22") (pin "2") (pinfunction "2_2") (pintype "passive"))
      (node (ref "R23") (pin "2") (pinfunction "2_2") (pintype "passive"))
      (node (ref "R24") (pin "2") (pinfunction "2_2") (pintype "passive"))
      (node (ref "R25") (pin "1") (pinfunction "1_1") (pintype "passive"))
      (node (ref "R28") (pin "2") (pinfunction "2_2") (pintype "passive"))
      (node (ref "R3") (pin "1") (pinfunction "1_1") (pintype "passive"))
      (node (ref "R5") (pin "1") (pinfunction "1_1") (pintype "passive"))
      (node (ref "R6") (pin "1") (pinfunction "1_1") (pintype "passive"))
      (node (ref "TP3") (pin "1") (pinfunction "TP_1") (pintype "passive"))
      (node (ref "TP4") (pin "1") (pinfunction "TP_1") (pintype "passive"))
      (node (ref "TP43") (pin "1") (pinfunction "TP_1") (pintype "passive"))
      (node (ref "TP5") (pin "1") (pinfunction "TP_1") (pintype "passive"))
      (node (ref "U3") (pin "2") (pinfunction "3V3_2") (pintype "power_in"))
      (node (ref "U7") (pin "6") (pinfunction "VDD_6") (pintype "power_in"))
      (node (ref "U8") (pin "13") (pinfunction "VDD_13") (pintype "power_in"))
      (node (ref "U8") (pin "8") (pinfunction "VLOGIC_8") (pintype "power_in"))
      (node (ref "U9") (pin "6") (pinfunction "VOS_6") (pintype "input"))
    )
    (net (code "2") (name "+GND") (class "Default")
      (node (ref "C1") (pin "1") (pinfunction "1_1") (pintype "passive"))
      (node (ref "C11") (pin "2") (pinfunction "2_2") (pintype "passive"))
      (node (ref "C12") (pin "1") (pinfunction "1_1") (pintype "passive"))
      (node (ref "C13") (pin "1") (pinfunction "1_1") (pintype "passive"))
      (node (ref "C14") (pin "2") (pinfunction "2_2") (pintype "passive"))
      (node (ref "C15") (pin "2") (pinfunction "2_2") (pintype "passive"))
      (node (ref "C16") (pin "2") (pinfunction "2_2") (pintype "passive"))
      (node (ref "C17") (pin "1") (pinfunction "1_1") (pintype "passive"))
      (node (ref "C18") (pin "2") (pinfunction "2_2") (pintype "passive"))
      (node (ref "C19") (pin "1") (pinfunction "1_1") (pintype "passive"))
      (node (ref "C2") (pin "1") (pinfunction "1_1") (pintype "passive"))
      (node (ref "C20") (pin "2") (pinfunction "2_2") (pintype "passive"))
      (node (ref "C21") (pin "2") (pinfunction "2_2") (pintype "passive"))
      (node (ref "C22") (pin "2") (pinfunction "2_2") (pintype "passive"))
      (node (ref "C4") (pin "1") (pinfunction "1_1") (pintype "passive"))
      (node (ref "C5") (pin "1") (pinfunction "1_1") (pintype "passive"))
      (node (ref "C6") (pin "1") (pinfunction "1_1") (pintype "passive"))
      (node (ref "C7") (pin "1") (pinfunction "1_1") (pintype "passive"))
      (node (ref "C8") (pin "1") (pinfunction "1_1") (pintype "passive"))
      (node (ref "C9") (pin "1") (pinfunction "1_1") (pintype "passive"))
      (node (ref "J1") (pin "A1") (pinfunction "GND1_A1") (pintype "passive"))
      (node (ref "J1") (pin "A12") (pinfunction "GND2_A12") (pintype "passive"))
      (node (ref "J1") (pin "B1") (pinfunction "GND3_B1") (pintype "passive"))
      (node (ref "J1") (pin "B12") (pinfunction "GND4_B12") (pintype "passive"))
      (node (ref "J1") (pin "S1") (pinfunction "SHIELD_S1") (pintype "passive"))
      (node (ref "J1") (pin "S2") (pinfunction "SHIELD_S2") (pintype "passive"))
      (node (ref "J1") (pin "S3") (pinfunction "SHIELD_S3") (pintype "passive"))
      (node (ref "J1") (pin "S4") (pinfunction "SHIELD_S4") (pintype "passive"))
      (node (ref "J2") (pin "1") (pinfunction "GND_1") (pintype "passive"))
      (node (ref "J2") (pin "2") (pinfunction "GND_2") (pintype "passive"))
      (node (ref "J2") (pin "3") (pinfunction "GND_3") (pintype "passive"))
      (node (ref "J2") (pin "8") (pinfunction "GND_8") (pintype "passive"))
      (node (ref "J4") (pin "4") (pinfunction "4_4") (pintype "passive"))
      (node (ref "J5") (pin "6") (pinfunction "6_6") (pintype "passive"))
      (node (ref "R10") (pin "1") (pinfunction "1_1") (pintype "passive"))
      (node (ref "R13") (pin "2") (pinfunction "2_2") (pintype "passive"))
      (node (ref "R14") (pin "1") (pinfunction "1_1") (pintype "passive"))
      (node (ref "R15") (pin "1") (pinfunction "1_1") (pintype "passive"))
      (node (ref "R26") (pin "1") (pinfunction "1_1") (pintype "passive"))
      (node (ref "R4") (pin "1") (pinfunction "1_1") (pintype "passive"))
      (node (ref "R7") (pin "2") (pinfunction "2_2") (pintype "passive"))
      (node (ref "R9") (pin "2") (pinfunction "2_2") (pintype "passive"))
      (node (ref "S4") (pin "1") (pinfunction "1_1") (pintype "passive"))
      (node (ref "S4") (pin "3") (pinfunction "3_3") (pintype "passive"))
      (node (ref "S5") (pin "1") (pinfunction "1_1") (pintype "passive"))
      (node (ref "S5") (pin "3") (pinfunction "3_3") (pintype "passive"))
      (node (ref "S6") (pin "1") (pinfunction "1_1") (pintype "passive"))
      (node (ref "S6") (pin "3") (pinfunction "3_3") (pintype "passive"))
      (node (ref "TP37") (pin "1") (pinfunction "TP_1") (pintype "passive"))
      (node (ref "TP40") (pin "1") (pinfunction "TP_1") (pintype "passive"))
      (node (ref "U2") (pin "1") (pinfunction "S1_1") (pintype "passive"))
      (node (ref "U3") (pin "1") (pinfunction "GND_1") (pintype "power_in"))
      (node (ref "U3") (pin "15") (pinfunction "GND_15") (pintype "power_in"))
      (node (ref "U3") (pin "38") (pinfunction "GND_38") (pintype "power_in"))
      (node (ref "U3") (pin "39_1") (pinfunction "GND_39_1") (pintype "power_in"))
      (node (ref "U3") (pin "39_10") (pinfunction "GND_39_10") (pintype "power_in"))
      (node (ref "U3") (pin "39_11") (pinfunction "GND_39_11") (pintype "power_in"))
      (node (ref "U3") (pin "39_12") (pinfunction "GND_39_12") (pintype "power_in"))
      (node (ref "U3") (pin "39_13") (pinfunction "GND_39_13") (pintype "power_in"))
      (node (ref "U3") (pin "39_14") (pinfunction "GND_39_14") (pintype "power_in"))
      (node (ref "U3") (pin "39_15") (pinfunction "GND_39_15") (pintype "power_in"))
      (node (ref "U3") (pin "39_16") (pinfunction "GND_39_16") (pintype "power_in"))
      (node (ref "U3") (pin "39_17") (pinfunction "GND_39_17") (pintype "power_in"))
      (node (ref "U3") (pin "39_18") (pinfunction "GND_39_18") (pintype "power_in"))
      (node (ref "U3") (pin "39_19") (pinfunction "GND_39_19") (pintype "power_in"))
      (node (ref "U3") (pin "39_2") (pinfunction "GND_39_2") (pintype "power_in"))
      (node (ref "U3") (pin "39_20") (pinfunction "GND_39_20") (pintype "power_in"))
      (node (ref "U3") (pin "39_21") (pinfunction "GND_39_21") (pintype "power_in"))
      (node (ref "U3") (pin "39_3") (pinfunction "GND_39_3") (pintype "power_in"))
      (node (ref "U3") (pin "39_4") (pinfunction "GND_39_4") (pintype "power_in"))
      (node (ref "U3") (pin "39_5") (pinfunction "GND_39_5") (pintype "power_in"))
      (node (ref "U3") (pin "39_6") (pinfunction "GND_39_6") (pintype "power_in"))
      (node (ref "U3") (pin "39_7") (pinfunction "GND_39_7") (pintype "power_in"))
      (node (ref "U3") (pin "39_8") (pinfunction "GND_39_8") (pintype "power_in"))
      (node (ref "U3") (pin "39_9") (pinfunction "GND_39_9") (pintype "power_in"))
      (node (ref "U4") (pin "10") (pinfunction "GND_10") (pintype "power_in"))
      (node (ref "U4") (pin "5") (pinfunction "GND_5") (pintype "power_in"))
      (node (ref "U4") (pin "8") (pinfunction "GND_8") (pintype "power_in"))
      (node (ref "U5") (pin "3") (pinfunction "S_3") (pintype "passive"))
      (node (ref "U6") (pin "14") (pinfunction "TMR_14") (pintype "input"))
      (node (ref "U6") (pin "17") (pinfunction "EXP_17") (pintype "power_in"))
      (node (ref "U6") (pin "4") (pinfunction "~{CE}_4") (pintype "input"))
      (node (ref "U6") (pin "6") (pinfunction "EN1_6") (pintype "input"))
      (node (ref "U6") (pin "8") (pinfunction "VSS_8") (pintype "power_in"))
      (node (ref "U7") (pin "7") (pinfunction "GND_7") (pintype "power_in"))
      (node (ref "U8") (pin "1") (pinfunction "CLKIN_1") (pintype "input"))
      (node (ref "U8") (pin "11") (pinfunction "FSYNC_11") (pintype "input"))
      (node (ref "U8") (pin "9") (pinfunction "AD0_9") (pintype "input"))
      (node (ref "U9") (pin "1") (pinfunction "PGND_1") (pintype "power_in"))
      (node (ref "U9") (pin "4") (pinfunction "AGND_4") (pintype "power_in"))
      (node (ref "U9") (pin "5") (pinfunction "FB_5") (pintype "input"))
      (node (ref "U9") (pin "9") (pinfunction "EXP_9") (pintype "passive"))
    )
    (net (code "3") (name "+VPMIC") (class "Default")
      (node (ref "C17") (pin "2") (pinfunction "2_2") (pintype "passive"))
      (node (ref "C6") (pin "2") (pinfunction "2_2") (pintype "passive"))
      (node (ref "C8") (pin "2") (pinfunction "2_2") (pintype "passive"))
      (node (ref "TP13") (pin "1") (pinfunction "TP_1") (pintype "passive"))
      (node (ref "U4") (pin "7") (pinfunction "VDD_7") (pintype "power_in"))
      (node (ref "U6") (pin "10") (pinfunction "OUT_10_10") (pintype "output"))
      (node (ref "U6") (pin "11") (pinfunction "OUT_11_11") (pintype "output"))
      (node (ref "U6") (pin "5") (pinfunction "EN2_5") (pintype "input"))
      (node (ref "U9") (pin "2") (pinfunction "VIN_2") (pintype "input"))
      (node (ref "U9") (pin "3") (pinfunction "EN_3") (pintype "input"))
    )
    (net (code "4") (name "/+5VUSB") (class "Default")
      (node (ref "C7") (pin "2") (pinfunction "2_2") (pintype "passive"))
      (node (ref "J1") (pin "A4") (pinfunction "VBUS1_A4") (pintype "passive"))
      (node (ref "J1") (pin "A9") (pinfunction "VBUS2_A9") (pintype "passive"))
      (node (ref "J1") (pin "B4") (pinfunction "VBUS3_B4") (pintype "passive"))
      (node (ref "J1") (pin "B9") (pinfunction "VBUS4_B9") (pintype "passive"))
      (node (ref "TP30") (pin "1") (pinfunction "TP_1") (pintype "passive"))
      (node (ref "U6") (pin "13") (pinfunction "IN_13") (pintype "input"))
    )
    (net (code "5") (name "/AUDIO_AMP_IN") (class "Default")
      (node (ref "C10") (pin "1") (pinfunction "1_1") (pintype "passive"))
      (node (ref "TP32") (pin "1") (pinfunction "TP_1") (pintype "passive"))
      (node (ref "U3") (pin "16") (pinfunction "IO13_16") (pintype "bidirectional"))
    )
    (net (code "6") (name "/BAT+") (class "Default")
      (node (ref "C9") (pin "2") (pinfunction "2_2") (pintype "passive"))
      (node (ref "J3") (pin "1") (pinfunction "1_1") (pintype "passive"))
      (node (ref "R1") (pin "2") (pinfunction "2_2") (pintype "passive"))
      (node (ref "TP28") (pin "1") (pinfunction "TP_1") (pintype "passive"))
      (node (ref "U6") (pin "2") (pinfunction "BAT_2_2") (pintype "bidirectional"))
      (node (ref "U6") (pin "3") (pinfunction "BAT_3_3") (pintype "bidirectional"))
    )
    (net (code "7") (name "/BAT-") (class "Default")
      (node (ref "C3") (pin "1") (pinfunction "1_1") (pintype "passive"))
      (node (ref "J3") (pin "2") (pinfunction "2_2") (pintype "passive"))
      (node (ref "R8") (pin "1") (pinfunction "1_1") (pintype "passive"))
      (node (ref "TP29") (pin "1") (pinfunction "TP_1") (pintype "passive"))
      (node (ref "U1") (pin "4") (pinfunction "VSS_4") (pintype "passive"))
      (node (ref "U2") (pin "3") (pinfunction "S2_3") (pintype "passive"))
    )
    (net (code "8") (name "/BUTTON") (class "Default")
      (node (ref "C22") (pin "1") (pinfunction "1_1") (pintype "passive"))
      (node (ref "S6") (pin "2") (pinfunction "2_2") (pintype "passive"))
      (node (ref "S6") (pin "4") (pinfunction "4_4") (pintype "passive"))
      (node (ref "TP47") (pin "1") (pinfunction "TP_1") (pintype "passive"))
      (node (ref "U3") (pin "6") (pinfunction "IO34_6") (pintype "input"))
    )
    (net (code "9") (name "/CHAR_CHG") (class "Default")
      (node (ref "TP11") (pin "1") (pinfunction "TP_1") (pintype "passive"))
      (node (ref "U3") (pin "4") (pinfunction "SENSOR_VP_4") (pintype "input"))
      (node (ref "U6") (pin "9") (pinfunction "~{CHG}_9") (pintype "output"))
    )
    (net (code "10") (name "/CHAR_PGOOD") (class "Default")
      (node (ref "TP12") (pin "1") (pinfunction "TP_1") (pintype "passive"))
      (node (ref "U3") (pin "5") (pinfunction "SENSOR_VN_5") (pintype "input"))
      (node (ref "U6") (pin "7") (pinfunction "~{PGOOD}_7") (pintype "output"))
    )
    (net (code "11") (name "/DEBUG") (class "Default")
      (node (ref "TP39") (pin "1") (pinfunction "TP_1") (pintype "passive"))
      (node (ref "U3") (pin "24") (pinfunction "IO2_24") (pintype "bidirectional"))
    )
    (net (code "12") (name "/DTR") (class "Default")
      (node (ref "J4") (pin "2") (pinfunction "2_2") (pintype "passive"))
      (node (ref "J5") (pin "4") (pinfunction "4_4") (pintype "passive"))
      (node (ref "Q2") (pin "2") (pinfunction "E_2") (pintype "passive"))
      (node (ref "R21") (pin "1") (pinfunction "1_1") (pintype "passive"))
      (node (ref "TP34") (pin "1") (pinfunction "TP_1") (pintype "passive"))
    )
    (net (code "13") (name "/ESP32_BOOT") (class "Default")
      (node (ref "C14") (pin "1") (pinfunction "1_1") (pintype "passive"))
      (node (ref "Q2") (pin "3") (pinfunction "C_3") (pintype "passive"))
      (node (ref "S4") (pin "2") (pinfunction "2_2") (pintype "passive"))
      (node (ref "S4") (pin "4") (pinfunction "4_4") (pintype "passive"))
      (node (ref "TP41") (pin "1") (pinfunction "TP_1") (pintype "passive"))
      (node (ref "U3") (pin "25") (pinfunction "IO0_25") (pintype "bidirectional"))
    )
    (net (code "14") (name "/ESP32_EN") (class "Default")
      (node (ref "C13") (pin "2") (pinfunction "2_2") (pintype "passive"))
      (node (ref "C18") (pin "1") (pinfunction "1_1") (pintype "passive"))
      (node (ref "Q1") (pin "3") (pinfunction "C_3") (pintype "passive"))
      (node (ref "R24") (pin "1") (pinfunction "1_1") (pintype "passive"))
      (node (ref "S5") (pin "2") (pinfunction "2_2") (pintype "passive"))
      (node (ref "S5") (pin "4") (pinfunction "4_4") (pintype "passive"))
      (node (ref "TP42") (pin "1") (pinfunction "TP_1") (pintype "passive"))
      (node (ref "U3") (pin "3") (pinfunction "EN_3") (pintype "input"))
    )
    (net (code "15") (name "/ESP32_RXD0") (class "Default")
      (node (ref "J4") (pin "6") (pinfunction "6_6") (pintype "passive"))
      (node (ref "J5") (pin "3") (pinfunction "3_3") (pintype "passive"))
      (node (ref "TP33") (pin "1") (pinfunction "TP_1") (pintype "passive"))
      (node (ref "U3") (pin "34") (pinfunction "RXD0_34") (pintype "bidirectional"))
    )
    (net (code "16") (name "/ESP32_TXD0") (class "Default")
      (node (ref "J4") (pin "5") (pinfunction "5_5") (pintype "passive"))
      (node (ref "J5") (pin "2") (pinfunction "2_2") (pintype "passive"))
      (node (ref "TP31") (pin "1") (pinfunction "TP_1") (pintype "passive"))
      (node (ref "U3") (pin "35") (pinfunction "TXD0_35") (pintype "bidirectional"))
    )
    (net (code "17") (name "/I2C_SCL") (class "Default")
      (node (ref "J2") (pin "7") (pinfunction "CTP_SCL_7") (pintype "passive"))
      (node (ref "R23") (pin "1") (pinfunction "1_1") (pintype "passive"))
      (node (ref "TP22") (pin "1") (pinfunction "TP_1") (pintype "passive"))
      (node (ref "TP45") (pin "1") (pinfunction "TP_1") (pintype "passive"))
      (node (ref "U3") (pin "12") (pinfunction "IO27_12") (pintype "bidirectional"))
      (node (ref "U8") (pin "23") (pinfunction "SCL_23") (pintype "input"))
    )
    (net (code "18") (name "/I2C_SDA") (class "Default")
      (node (ref "J2") (pin "6") (pinfunction "CTP_SDA_6") (pintype "passive"))
      (node (ref "R22") (pin "1") (pinfunction "1_1") (pintype "passive"))
      (node (ref "TP23") (pin "1") (pinfunction "TP_1") (pintype "passive"))
      (node (ref "TP46") (pin "1") (pinfunction "TP_1") (pintype "passive"))
      (node (ref "U3") (pin "11") (pinfunction "IO26_11") (pintype "bidirectional"))
      (node (ref "U8") (pin "24") (pinfunction "SDA_24") (pintype "bidirectional"))
    )
    (net (code "19") (name "/IMU_INT") (class "Default")
      (node (ref "TP44") (pin "1") (pinfunction "TP_1") (pintype "passive"))
      (node (ref "U3") (pin "7") (pinfunction "IO35_7") (pintype "input"))
      (node (ref "U8") (pin "12") (pinfunction "INT_12") (pintype "output"))
    )
    (net (code "20") (name "/LCD_CS") (class "Default")
      (node (ref "J2") (pin "13") (pinfunction "CS_13") (pintype "passive"))
      (node (ref "TP19") (pin "1") (pinfunction "TP_1") (pintype "passive"))
      (node (ref "U3") (pin "33") (pinfunction "IO21_33") (pintype "bidirectional"))
    )
    (net (code "21") (name "/LCD_LEDK") (class "Default")
      (node (ref "J2") (pin "50") (pinfunction "LEDK_50") (pintype "passive"))
      (node (ref "TP1") (pin "1") (pinfunction "TP_1") (pintype "passive"))
      (node (ref "U5") (pin "1") (pinfunction "D_1") (pintype "passive"))
    )
    (net (code "22") (name "/LCD_LEDS") (class "Default")
      (node (ref "R12") (pin "1") (pinfunction "1_1") (pintype "passive"))
      (node (ref "TP8") (pin "1") (pinfunction "TP_1") (pintype "passive"))
      (node (ref "U3") (pin "26") (pinfunction "IO4_26") (pintype "bidirectional"))
      (node (ref "U5") (pin "2") (pinfunction "G_2") (pintype "passive"))
    )
    (net (code "23") (name "/LCD_RD") (class "Default")
      (node (ref "J2") (pin "16") (pinfunction "RD_16") (pintype "passive"))
      (node (ref "TP16") (pin "1") (pinfunction "TP_1") (pintype "passive"))
      (node (ref "U3") (pin "29") (pinfunction "IO5_29") (pintype "bidirectional"))
    )
    (net (code "24") (name "/LCD_RESET") (class "Default")
      (node (ref "J2") (pin "4") (pinfunction "CTP_RES_4") (pintype "passive"))
      (node (ref "J2") (pin "41") (pinfunction "RESET_41") (pintype "passive"))
      (node (ref "TP26") (pin "1") (pinfunction "TP_1") (pintype "passive"))
      (node (ref "U3") (pin "23") (pinfunction "IO15_23") (pintype "bidirectional"))
    )
    (net (code "25") (name "/LCD_RS_SCL") (class "Default")
      (node (ref "J2") (pin "14") (pinfunction "RS_SCL_14") (pintype "passive"))
      (node (ref "TP18") (pin "1") (pinfunction "TP_1") (pintype "passive"))
      (node (ref "U3") (pin "31") (pinfunction "IO19_31") (pintype "bidirectional"))
    )
    (net (code "26") (name "/LCD_SDI") (class "Default")
      (node (ref "J2") (pin "17") (pinfunction "SDI_17") (pintype "passive"))
      (node (ref "TP15") (pin "1") (pinfunction "TP_1") (pintype "passive"))
      (node (ref "U3") (pin "28") (pinfunction "IO17_28") (pintype "bidirectional"))
    )
    (net (code "27") (name "/LCD_SDO") (class "Default")
      (node (ref "J2") (pin "18") (pinfunction "SDO_18") (pintype "passive"))
      (node (ref "TP14") (pin "1") (pinfunction "TP_1") (pintype "passive"))
      (node (ref "U3") (pin "27") (pinfunction "IO16_27") (pintype "bidirectional"))
    )
    (net (code "28") (name "/LCD_TE") (class "Default")
      (node (ref "J2") (pin "12") (pinfunction "TE_12") (pintype "passive"))
      (node (ref "TP20") (pin "1") (pinfunction "TP_1") (pintype "passive"))
      (node (ref "U3") (pin "36") (pinfunction "IO22_36") (pintype "bidirectional"))
    )
    (net (code "29") (name "/LCD_TOUCH_IRQ") (class "Default")
      (node (ref "J2") (pin "5") (pinfunction "CTP_IRQ_5") (pintype "passive"))
      (node (ref "TP25") (pin "1") (pinfunction "TP_1") (pintype "passive"))
      (node (ref "U3") (pin "37") (pinfunction "IO23_37") (pintype "bidirectional"))
    )
    (net (code "30") (name "/LCD_WR_RS") (class "Default")
      (node (ref "J2") (pin "15") (pinfunction "WR_RS_15") (pintype "passive"))
      (node (ref "TP17") (pin "1") (pinfunction "TP_1") (pintype "passive"))
      (node (ref "U3") (pin "30") (pinfunction "IO18_30") (pintype "bidirectional"))
    )
    (net (code "31") (name "/LED_B") (class "Default")
      (node (ref "R18") (pin "2") (pinfunction "2_2") (pintype "passive"))
      (node (ref "TP27") (pin "1") (pinfunction "TP_1") (pintype "passive"))
      (node (ref "U3") (pin "8") (pinfunction "IO32_8") (pintype "bidirectional"))
    )
    (net (code "32") (name "/LED_G") (class "Default")
      (node (ref "R17") (pin "2") (pinfunction "2_2") (pintype "passive"))
      (node (ref "TP24") (pin "1") (pinfunction "TP_1") (pintype "passive"))
      (node (ref "U3") (pin "9") (pinfunction "IO33_9") (pintype "bidirectional"))
    )
    (net (code "33") (name "/LED_R") (class "Default")
      (node (ref "R16") (pin "2") (pinfunction "2_2") (pintype "passive"))
      (node (ref "TP21") (pin "1") (pinfunction "TP_1") (pintype "passive"))
      (node (ref "U3") (pin "10") (pinfunction "IO25_10") (pintype "bidirectional"))
    )
    (net (code "34") (name "/MOTOR+") (class "Default")
      (node (ref "M1") (pin "1") (pinfunction "V+_1") (pintype "power_in"))
      (node (ref "TP9") (pin "1") (pinfunction "TP_1") (pintype "passive"))
      (node (ref "U4") (pin "9") (pinfunction "OUT_P_9") (pintype "output"))
    )
    (net (code "35") (name "/MOTOR-") (class "Default")
      (node (ref "M1") (pin "2") (pinfunction "V-_2") (pintype "power_in"))
      (node (ref "TP10") (pin "1") (pinfunction "TP_1") (pintype "passive"))
      (node (ref "U4") (pin "6") (pinfunction "OUT_M_6") (pintype "output"))
    )
    (net (code "36") (name "/MOTOR_EN") (class "Default")
      (node (ref "TP6") (pin "1") (pinfunction "TP_1") (pintype "passive"))
      (node (ref "U3") (pin "14") (pinfunction "IO12_14") (pintype "bidirectional"))
      (node (ref "U4") (pin "1") (pinfunction "EN_1") (pintype "input"))
    )
    (net (code "37") (name "/MOTOR_PWM") (class "Default")
      (node (ref "TP7") (pin "1") (pinfunction "TP_1") (pintype "passive"))
      (node (ref "U3") (pin "13") (pinfunction "IO14_13") (pintype "bidirectional"))
      (node (ref "U4") (pin "2") (pinfunction "PWM_2") (pintype "input"))
    )
    (net (code "38") (name "/RTS") (class "Default")
      (node (ref "J4") (pin "3") (pinfunction "3_3") (pintype "passive"))
      (node (ref "J5") (pin "5") (pinfunction "5_5") (pintype "passive"))
      (node (ref "Q1") (pin "2") (pinfunction "E_2") (pintype "passive"))
      (node (ref "R27") (pin "1") (pinfunction "1_1") (pintype "passive"))
      (node (ref "TP35") (pin "1") (pinfunction "TP_1") (pintype "passive"))
    )
    (net (code "39") (name "/SPEAKER_+") (class "Default")
      (node (ref "R19") (pin "2") (pinfunction "2_2") (pintype "passive"))
      (node (ref "TP36") (pin "1") (pinfunction "TP_1") (pintype "passive"))
      (node (ref "U7") (pin "5") (pinfunction "VO1_5") (pintype "output"))
    )
    (net (code "40") (name "/SPEAKER_-") (class "Default")
      (node (ref "TP38") (pin "1") (pinfunction "TP_1") (pintype "passive"))
      (node (ref "U7") (pin "8") (pinfunction "VO2_8") (pintype "output"))
    )
    (net (code "41") (name "Net-(C10-Pad2)") (class "Default")
      (node (ref "C10") (pin "2") (pinfunction "2_2") (pintype "passive"))
      (node (ref "R20") (pin "1") (pinfunction "1_1") (pintype "passive"))
    )
    (net (code "42") (name "Net-(J2-IM0)") (class "Default")
      (node (ref "J2") (pin "45") (pinfunction "IM0_45") (pintype "passive"))
      (node (ref "R9") (pin "1") (pinfunction "1_1") (pintype "passive"))
      (node (ref "TP2") (pin "1") (pinfunction "TP_1") (pintype "passive"))
    )
    (net (code "43") (name "Net-(J2-LED-A1)") (class "Default")
      (node (ref "J2") (pin "49") (pinfunction "LED-A1_49") (pintype "passive"))
      (node (ref "R2") (pin "2") (pinfunction "2_2") (pintype "passive"))
    )
    (net (code "44") (name "Net-(J2-LED-A2)") (class "Default")
      (node (ref "J2") (pin "48") (pinfunction "LED-A2_48") (pintype "passive"))
      (node (ref "R3") (pin "2") (pinfunction "2_2") (pintype "passive"))
    )
    (net (code "45") (name "Net-(J2-LED-A3)") (class "Default")
      (node (ref "J2") (pin "47") (pinfunction "LED-A3_47") (pintype "passive"))
      (node (ref "R5") (pin "2") (pinfunction "2_2") (pintype "passive"))
    )
    (net (code "46") (name "Net-(J2-LED-A4)") (class "Default")
      (node (ref "J2") (pin "46") (pinfunction "LED-A4_46") (pintype "passive"))
      (node (ref "R6") (pin "2") (pinfunction "2_2") (pintype "passive"))
    )
    (net (code "47") (name "Net-(LED1-B)") (class "Default")
      (node (ref "LED1") (pin "3") (pinfunction "B_3") (pintype "passive"))
      (node (ref "R18") (pin "1") (pinfunction "1_1") (pintype "passive"))
    )
    (net (code "48") (name "Net-(LED1-G)") (class "Default")
      (node (ref "LED1") (pin "2") (pinfunction "G_2") (pintype "passive"))
      (node (ref "R17") (pin "1") (pinfunction "1_1") (pintype "passive"))
    )
    (net (code "49") (name "Net-(LED1-R)") (class "Default")
      (node (ref "LED1") (pin "1") (pinfunction "R_1") (pintype "passive"))
      (node (ref "R16") (pin "1") (pinfunction "1_1") (pintype "passive"))
    )
    (net (code "50") (name "Net-(Q1-B)") (class "Default")
      (node (ref "Q1") (pin "1") (pinfunction "B_1") (pintype "passive"))
      (node (ref "R21") (pin "2") (pinfunction "2_2") (pintype "passive"))
    )
    (net (code "51") (name "Net-(Q2-B)") (class "Default")
      (node (ref "Q2") (pin "1") (pinfunction "B_1") (pintype "passive"))
      (node (ref "R27") (pin "2") (pinfunction "2_2") (pintype "passive"))
    )
    (net (code "52") (name "Net-(U1-BAT)") (class "Default")
      (node (ref "C3") (pin "2") (pinfunction "2_2") (pintype "passive"))
      (node (ref "R1") (pin "1") (pinfunction "1_1") (pintype "passive"))
      (node (ref "U1") (pin "5") (pinfunction "BAT_5") (pintype "passive"))
    )
    (net (code "53") (name "Net-(U1-COUT)") (class "Default")
      (node (ref "R7") (pin "1") (pinfunction "1_1") (pintype "passive"))
      (node (ref "U1") (pin "2") (pinfunction "COUT_2") (pintype "passive"))
      (node (ref "U2") (pin "2") (pinfunction "G1_2") (pintype "passive"))
    )
    (net (code "54") (name "Net-(U1-DOUT)") (class "Default")
      (node (ref "R8") (pin "2") (pinfunction "2_2") (pintype "passive"))
      (node (ref "U1") (pin "3") (pinfunction "DOUT_3") (pintype "passive"))
      (node (ref "U2") (pin "4") (pinfunction "G2_4") (pintype "passive"))
    )
    (net (code "55") (name "Net-(U1-V-)") (class "Default")
      (node (ref "R4") (pin "2") (pinfunction "2_2") (pintype "passive"))
      (node (ref "U1") (pin "6") (pinfunction "V-_6") (pintype "passive"))
    )
    (net (code "56") (name "Net-(U2-D-Pad5)") (class "Default")
      (node (ref "U2") (pin "5") (pinfunction "D_5") (pintype "passive"))
      (node (ref "U2") (pin "6") (pinfunction "D_6") (pintype "passive"))
      (node (ref "U2") (pin "7") (pinfunction "D_7") (pintype "passive"))
      (node (ref "U2") (pin "8") (pinfunction "D_8") (pintype "passive"))
    )
    (net (code "57") (name "Net-(U4-LRA{slash}!ERM)") (class "Default")
      (node (ref "R10") (pin "2") (pinfunction "2_2") (pintype "passive"))
      (node (ref "R11") (pin "2") (pinfunction "2_2") (pintype "passive"))
      (node (ref "U4") (pin "3") (pinfunction "LRA/!ERM_3") (pintype "input"))
    )
    (net (code "58") (name "Net-(U6-ILIM)") (class "Default")
      (node (ref "R14") (pin "2") (pinfunction "2_2") (pintype "passive"))
      (node (ref "U6") (pin "12") (pinfunction "ILIM_12") (pintype "input"))
    )
    (net (code "59") (name "Net-(U6-ISET)") (class "Default")
      (node (ref "R15") (pin "2") (pinfunction "2_2") (pintype "passive"))
      (node (ref "U6") (pin "16") (pinfunction "ISET_16") (pintype "bidirectional"))
    )
    (net (code "60") (name "Net-(U6-TS)") (class "Default")
      (node (ref "R13") (pin "1") (pinfunction "1_1") (pintype "passive"))
      (node (ref "U6") (pin "1") (pinfunction "TS_1") (pintype "input"))
    )
    (net (code "61") (name "Net-(U7-+IN)") (class "Default")
      (node (ref "C11") (pin "1") (pinfunction "1_1") (pintype "passive"))
      (node (ref "U7") (pin "2") (pinfunction "BYPASS_2") (pintype "input"))
      (node (ref "U7") (pin "3") (pinfunction "+IN_3") (pintype "input"))
    )
    (net (code "62") (name "Net-(U7--IN)") (class "Default")
      (node (ref "R19") (pin "1") (pinfunction "1_1") (pintype "passive"))
      (node (ref "R20") (pin "2") (pinfunction "2_2") (pintype "passive"))
      (node (ref "U7") (pin "4") (pinfunction "-IN_4") (pintype "input"))
    )
    (net (code "63") (name "Net-(U7-~{SHDN})") (class "Default")
      (node (ref "R25") (pin "2") (pinfunction "2_2") (pintype "passive"))
      (node (ref "R26") (pin "2") (pinfunction "2_2") (pintype "passive"))
      (node (ref "U7") (pin "1") (pinfunction "~{SHDN}_1") (pintype "input"))
    )
    (net (code "64") (name "Net-(U8-CPOUT)") (class "Default")
      (node (ref "C20") (pin "1") (pinfunction "1_1") (pintype "passive"))
      (node (ref "U8") (pin "20") (pinfunction "CPOUT_20") (pintype "passive"))
    )
    (net (code "65") (name "Net-(U8-REGOUT)") (class "Default")
      (node (ref "C21") (pin "1") (pinfunction "1_1") (pintype "passive"))
      (node (ref "U8") (pin "10") (pinfunction "REGOUT_10") (pintype "passive"))
    )
    (net (code "66") (name "Net-(U9-PG)") (class "Default")
      (node (ref "R28") (pin "1") (pinfunction "1_1") (pintype "passive"))
      (node (ref "U9") (pin "8") (pinfunction "PG_8") (pintype "output"))
    )
    (net (code "67") (name "Net-(U9-SW)") (class "Default")
      (node (ref "L1") (pin "1") (pinfunction "1_1") (pintype "passive"))
      (node (ref "U9") (pin "7") (pinfunction "SW_7") (pintype "output"))
    )
    (net (code "68") (name "unconnected-(J1-CC1-PadA5)") (class "Default")
      (node (ref "J1") (pin "A5") (pinfunction "CC1_A5") (pintype "passive+no_connect"))
    )
    (net (code "69") (name "unconnected-(J1-CC2-PadB5)") (class "Default")
      (node (ref "J1") (pin "B5") (pinfunction "CC2_B5") (pintype "passive+no_connect"))
    )
    (net (code "70") (name "unconnected-(J1-D1+-PadA6)") (class "Default")
      (node (ref "J1") (pin "A6") (pinfunction "D1+_A6") (pintype "passive+no_connect"))
    )
    (net (code "71") (name "unconnected-(J1-D1--PadA7)") (class "Default")
      (node (ref "J1") (pin "A7") (pinfunction "D1-_A7") (pintype "passive+no_connect"))
    )
    (net (code "72") (name "unconnected-(J1-D2+-PadB6)") (class "Default")
      (node (ref "J1") (pin "B6") (pinfunction "D2+_B6") (pintype "passive+no_connect"))
    )
    (net (code "73") (name "unconnected-(J1-D2--PadB7)") (class "Default")
      (node (ref "J1") (pin "B7") (pinfunction "D2-_B7") (pintype "passive+no_connect"))
    )
    (net (code "74") (name "unconnected-(J1-RX1+-PadB11)") (class "Default")
      (node (ref "J1") (pin "B11") (pinfunction "RX1+_B11") (pintype "passive+no_connect"))
    )
    (net (code "75") (name "unconnected-(J1-RX1--PadB10)") (class "Default")
      (node (ref "J1") (pin "B10") (pinfunction "RX1-_B10") (pintype "passive+no_connect"))
    )
    (net (code "76") (name "unconnected-(J1-RX2+-PadA11)") (class "Default")
      (node (ref "J1") (pin "A11") (pinfunction "RX2+_A11") (pintype "passive+no_connect"))
    )
    (net (code "77") (name "unconnected-(J1-RX2--PadA10)") (class "Default")
      (node (ref "J1") (pin "A10") (pinfunction "RX2-_A10") (pintype "passive+no_connect"))
    )
    (net (code "78") (name "unconnected-(J1-SBU1-PadA8)") (class "Default")
      (node (ref "J1") (pin "A8") (pinfunction "SBU1_A8") (pintype "passive+no_connect"))
    )
    (net (code "79") (name "unconnected-(J1-SBU2-PadB8)") (class "Default")
      (node (ref "J1") (pin "B8") (pinfunction "SBU2_B8") (pintype "passive+no_connect"))
    )
    (net (code "80") (name "unconnected-(J1-TX1+-PadA2)") (class "Default")
      (node (ref "J1") (pin "A2") (pinfunction "TX1+_A2") (pintype "passive+no_connect"))
    )
    (net (code "81") (name "unconnected-(J1-TX1--PadA3)") (class "Default")
      (node (ref "J1") (pin "A3") (pinfunction "TX1-_A3") (pintype "passive+no_connect"))
    )
    (net (code "82") (name "unconnected-(J1-TX2+-PadB2)") (class "Default")
      (node (ref "J1") (pin "B2") (pinfunction "TX2+_B2") (pintype "passive+no_connect"))
    )
    (net (code "83") (name "unconnected-(J1-TX2--PadB3)") (class "Default")
      (node (ref "J1") (pin "B3") (pinfunction "TX2-_B3") (pintype "passive+no_connect"))
    )
    (net (code "84") (name "unconnected-(J2-DB0-Pad19)") (class "Default")
      (node (ref "J2") (pin "19") (pinfunction "DB0_19") (pintype "passive+no_connect"))
    )
    (net (code "85") (name "unconnected-(J2-DB1-Pad20)") (class "Default")
      (node (ref "J2") (pin "20") (pinfunction "DB1_20") (pintype "passive+no_connect"))
    )
    (net (code "86") (name "unconnected-(J2-DB2-Pad21)") (class "Default")
      (node (ref "J2") (pin "21") (pinfunction "DB2_21") (pintype "passive+no_connect"))
    )
    (net (code "87") (name "unconnected-(J2-DB3-Pad22)") (class "Default")
      (node (ref "J2") (pin "22") (pinfunction "DB3_22") (pintype "passive+no_connect"))
    )
    (net (code "88") (name "unconnected-(J2-DB4-Pad23)") (class "Default")
      (node (ref "J2") (pin "23") (pinfunction "DB4_23") (pintype "passive+no_connect"))
    )
    (net (code "89") (name "unconnected-(J2-DB5-Pad24)") (class "Default")
      (node (ref "J2") (pin "24") (pinfunction "DB5_24") (pintype "passive+no_connect"))
    )
    (net (code "90") (name "unconnected-(J2-DB6-Pad25)") (class "Default")
      (node (ref "J2") (pin "25") (pinfunction "DB6_25") (pintype "passive+no_connect"))
    )
    (net (code "91") (name "unconnected-(J2-DB7-Pad26)") (class "Default")
      (node (ref "J2") (pin "26") (pinfunction "DB7_26") (pintype "passive+no_connect"))
    )
    (net (code "92") (name "unconnected-(J2-DB8-Pad27)") (class "Default")
      (node (ref "J2") (pin "27") (pinfunction "DB8_27") (pintype "passive+no_connect"))
    )
    (net (code "93") (name "unconnected-(J2-DB9-Pad28)") (class "Default")
      (node (ref "J2") (pin "28") (pinfunction "DB9_28") (pintype "passive+no_connect"))
    )
    (net (code "94") (name "unconnected-(J2-DB10-Pad29)") (class "Default")
      (node (ref "J2") (pin "29") (pinfunction "DB10_29") (pintype "passive+no_connect"))
    )
    (net (code "95") (name "unconnected-(J2-DB11-Pad30)") (class "Default")
      (node (ref "J2") (pin "30") (pinfunction "DB11_30") (pintype "passive+no_connect"))
    )
    (net (code "96") (name "unconnected-(J2-DB12-Pad31)") (class "Default")
      (node (ref "J2") (pin "31") (pinfunction "DB12_31") (pintype "passive+no_connect"))
    )
    (net (code "97") (name "unconnected-(J2-DB13-Pad32)") (class "Default")
      (node (ref "J2") (pin "32") (pinfunction "DB13_32") (pintype "passive+no_connect"))
    )
    (net (code "98") (name "unconnected-(J2-DB14-Pad33)") (class "Default")
      (node (ref "J2") (pin "33") (pinfunction "DB14_33") (pintype "passive+no_connect"))
    )
    (net (code "99") (name "unconnected-(J2-DB15-Pad34)") (class "Default")
      (node (ref "J2") (pin "34") (pinfunction "DB15_34") (pintype "passive+no_connect"))
    )
    (net (code "100") (name "unconnected-(J2-DB16-Pad35)") (class "Default")
      (node (ref "J2") (pin "35") (pinfunction "DB16_35") (pintype "passive+no_connect"))
    )
    (net (code "101") (name "unconnected-(J2-DB17-Pad36)") (class "Default")
      (node (ref "J2") (pin "36") (pinfunction "DB17_36") (pintype "passive+no_connect"))
    )
    (net (code "102") (name "unconnected-(J2-DE-Pad37)") (class "Default")
      (node (ref "J2") (pin "37") (pinfunction "DE_37") (pintype "passive+no_connect"))
    )
    (net (code "103") (name "unconnected-(J2-DOTCLK-Pad38)") (class "Default")
      (node (ref "J2") (pin "38") (pinfunction "DOTCLK_38") (pintype "passive+no_connect"))
    )
    (net (code "104") (name "unconnected-(J2-HSYNC-Pad39)") (class "Default")
      (node (ref "J2") (pin "39") (pinfunction "HSYNC_39") (pintype "passive+no_connect"))
    )
    (net (code "105") (name "unconnected-(J2-VSYNC-Pad40)") (class "Default")
      (node (ref "J2") (pin "40") (pinfunction "VSYNC_40") (pintype "passive+no_connect"))
    )
    (net (code "106") (name "unconnected-(J4-Pad1)") (class "Default")
      (node (ref "J4") (pin "1") (pinfunction "1_1") (pintype "passive+no_connect"))
    )
    (net (code "107") (name "unconnected-(J5-Pad1)") (class "Default")
      (node (ref "J5") (pin "1") (pinfunction "1_1") (pintype "passive+no_connect"))
    )
    (net (code "108") (name "unconnected-(U1-NC-Pad1)") (class "Default")
      (node (ref "U1") (pin "1") (pinfunction "NC_1") (pintype "passive+no_connect"))
    )
    (net (code "109") (name "unconnected-(U3-SCK{slash}CLK-Pad20)") (class "Default")
      (node (ref "U3") (pin "20") (pinfunction "SCK/CLK_20") (pintype "bidirectional+no_connect"))
    )
    (net (code "110") (name "unconnected-(U3-SCS{slash}CMD-Pad19)") (class "Default")
      (node (ref "U3") (pin "19") (pinfunction "SCS/CMD_19") (pintype "bidirectional+no_connect"))
    )
    (net (code "111") (name "unconnected-(U3-SDI{slash}SD1-Pad22)") (class "Default")
      (node (ref "U3") (pin "22") (pinfunction "SDI/SD1_22") (pintype "bidirectional+no_connect"))
    )
    (net (code "112") (name "unconnected-(U3-SDO{slash}SD0-Pad21)") (class "Default")
      (node (ref "U3") (pin "21") (pinfunction "SDO/SD0_21") (pintype "bidirectional+no_connect"))
    )
    (net (code "113") (name "unconnected-(U3-SHD{slash}SD2-Pad17)") (class "Default")
      (node (ref "U3") (pin "17") (pinfunction "SHD/SD2_17") (pintype "bidirectional+no_connect"))
    )
    (net (code "114") (name "unconnected-(U3-SWP{slash}SD3-Pad18)") (class "Default")
      (node (ref "U3") (pin "18") (pinfunction "SWP/SD3_18") (pintype "bidirectional+no_connect"))
    )
    (net (code "115") (name "unconnected-(U4-NC-Pad4)") (class "Default")
      (node (ref "U4") (pin "4") (pinfunction "NC_4") (pintype "power_in+no_connect"))
    )
    (net (code "116") (name "unconnected-(U6-ITERM-Pad15)") (class "Default")
      (node (ref "U6") (pin "15") (pinfunction "ITERM_15") (pintype "input+no_connect"))
    )
    (net (code "117") (name "unconnected-(U8-AUX_CL-Pad7)") (class "Default")
      (node (ref "U8") (pin "7") (pinfunction "AUX_CL_7") (pintype "input+no_connect"))
    )
    (net (code "118") (name "unconnected-(U8-AUX_DA-Pad6)") (class "Default")
      (node (ref "U8") (pin "6") (pinfunction "AUX_DA_6") (pintype "bidirectional+no_connect"))
    )
    (net (code "119") (name "unconnected-(U8-RESV-Pad22)") (class "Default")
      (node (ref "U8") (pin "22") (pinfunction "RESV_22") (pintype "passive+no_connect"))
    )
    (net (code "120") (name "unconnected-(U8-RESV@1-Pad19)") (class "Default")
      (node (ref "U8") (pin "19") (pinfunction "RESV@1_19") (pintype "passive+no_connect"))
    )
    (net (code "121") (name "unconnected-(U8-RESV@2-Pad21)") (class "Default")
      (node (ref "U8") (pin "21") (pinfunction "RESV@2_21") (pintype "passive+no_connect"))
    )
  )
)
